# ATmega32.net
KiCad netlist of a schematic drawn in Altium Designer
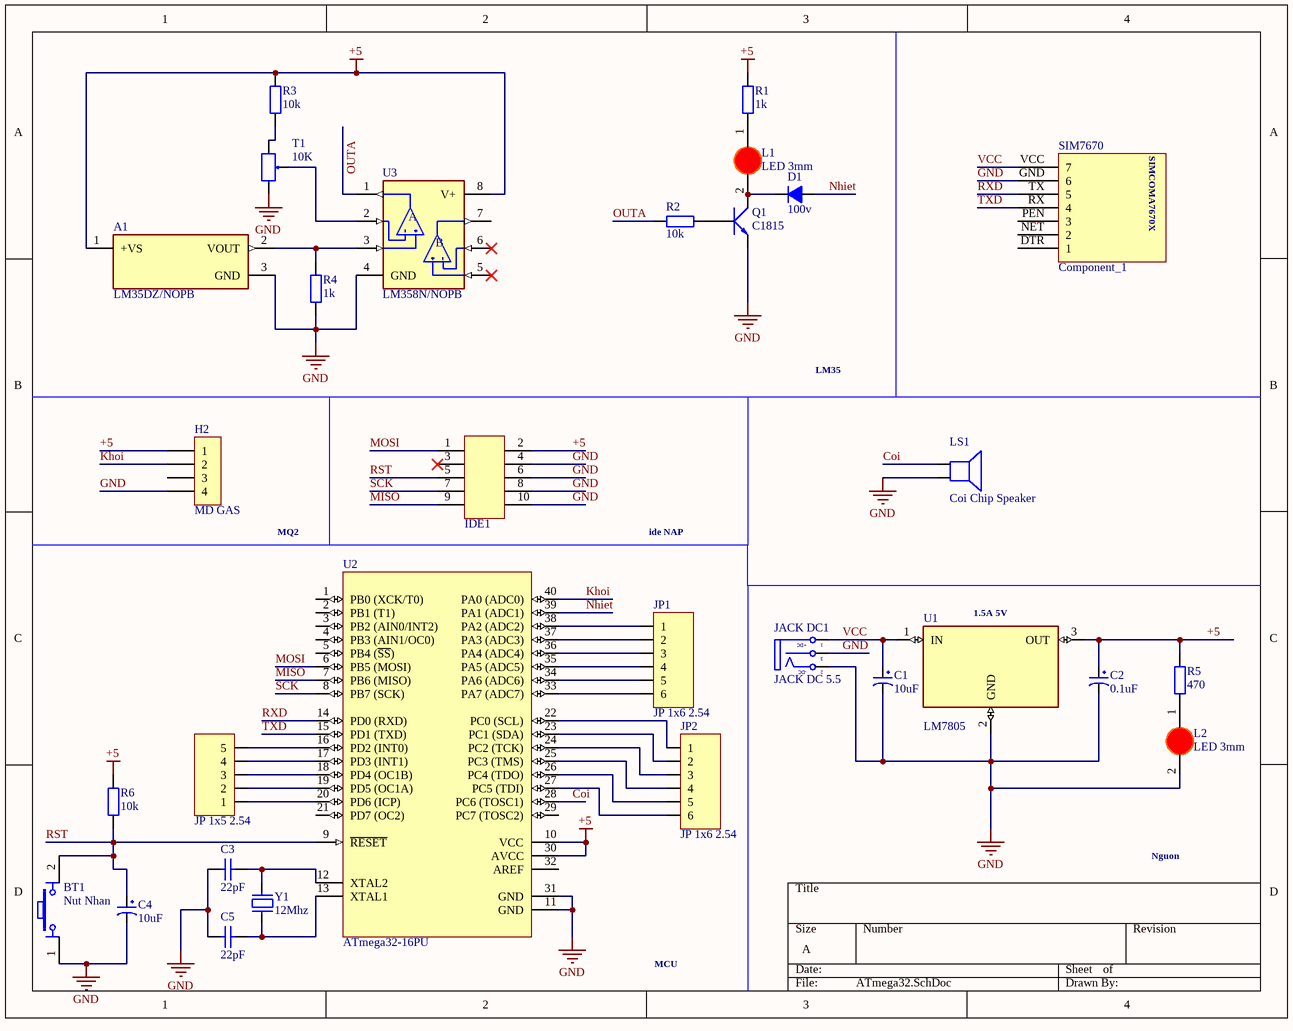
[diagram p0: ATmega32.SchDoc]

(export (version "E")
  (design (tool "Eeschema 10.0.6"))
  (components
    (comp (ref "A1")
      (value "LM35DZ/NOPB")
      (footprint "TO92127P521H735-3")
      (libsource (lib "LM35DZ_NOPB") (part "LM35DZ/NOPB"))
    )
    (comp (ref "BT1")
      (value "Nut Nhan")
      (footprint "Nut Nhan 4 Chan Cam 6x6")
      (description "Nut Nhan 4 Chan 6x6mm")
      (libsource (lib "Altium_Lib") (part "Nut Nhan 4 Chan Cam 6x6"))
    )
    (comp (ref "C1")
      (value "10uF")
      (footprint "tu hoa 4mm")
      (description "Cắm")
      (libsource (lib "Altium_Lib") (part "Tu Hoa 2.2uF 50V 4x7"))
    )
    (comp (ref "C2")
      (value "0.1uF")
      (footprint "tu hoa 4mm")
      (description "Cắm")
      (libsource (lib "Altium_Lib") (part "Tu Hoa 2.2uF 50V 4x7"))
    )
    (comp (ref "C3")
      (value "22pF")
      (footprint "tu gom")
      (description "Cắm")
      (libsource (lib "Altium_Lib") (part "Tu gom 22pF 50V"))
    )
    (comp (ref "C4")
      (value "10uF")
      (footprint "tu hoa 4mm")
      (description "Cắm")
      (libsource (lib "Altium_Lib") (part "Tu Hoa 10uF 25V 4x7"))
    )
    (comp (ref "C5")
      (value "22pF")
      (footprint "tu gom")
      (description "Cắm")
      (libsource (lib "Altium_Lib") (part "Tu gom 22pF 50V"))
    )
    (comp (ref "D1")
      (value "100v")
      (footprint "DIODE 1A")
      (description "Cắm")
      (libsource (lib "Altium_Lib") (part "Diode 1N4007"))
    )
    (comp (ref "H2")
      (value "MD GAS")
      (footprint "Header 4P DC 2.54")
      (description "Cắm")
      (libsource (lib "Altium_Lib") (part "Header 4P 2.54 Duc Cong"))
    )
    (comp (ref "IDE1")
      (value "IDE10")
      (footprint "IDE 10 DT")
      (libsource (lib "Altium_Lib") (part "IDE 10 DT"))
    )
    (comp (ref "JACK DC1")
      (value "JACK DC 5.5")
      (footprint "JACK DC 5.5")
      (libsource (lib "Altium_Lib") (part "JACK DC 5.5"))
    )
    (comp (ref "JP1")
      (value "JP 1x6 2.54")
      (footprint "JP 1x6 DT")
      (description "Cắm")
      (libsource (lib "Altium_Lib") (part "JP 1x6 2.54 Duc Thang"))
    )
    (comp (ref "JP2")
      (value "JP 1x6 2.54")
      (footprint "JP 1x6 DT")
      (description "Cắm")
      (libsource (lib "Altium_Lib") (part "JP 1x6 2.54 Duc Thang"))
    )
    (comp (ref "JP3")
      (value "JP 1x5 2.54")
      (footprint "JP 1x5 DT")
      (description "Cắm")
      (libsource (lib "Altium_Lib") (part "JP 1x5 2.54 Duc Thang"))
    )
    (comp (ref "L1")
      (value "LED 3mm")
      (footprint "LED-3MM-RED")
      (description "Cắm")
      (libsource (lib "Altium_Lib") (part "LED 3mm Do"))
    )
    (comp (ref "L2")
      (value "LED 3mm")
      (footprint "LED-3MM-RED")
      (description "Cắm")
      (libsource (lib "Altium_Lib") (part "LED 3mm Do"))
    )
    (comp (ref "LS1")
      (value "Coi Chip Speaker")
      (footprint "Coi Chip Speacker")
      (description "Còi chip")
      (libsource (lib "Altium_Lib") (part "Coi Chip Speaker"))
    )
    (comp (ref "Q1")
      (value "C1815")
      (footprint "TO92")
      (description "NPN transistor")
      (libsource (lib "Altium_Lib") (part "C1815"))
    )
    (comp (ref "R1")
      (value "1k")
      (footprint "tro vach 1/4w")
      (description "Căm")
      (libsource (lib "Altium_Lib") (part "Tro Vach 1/4W 5% 10k"))
    )
    (comp (ref "R2")
      (value "10k")
      (footprint "tro vach 1/4w")
      (description "Căm")
      (libsource (lib "Altium_Lib") (part "Tro Vach 1/4W 5% 10k"))
    )
    (comp (ref "R3")
      (value "10k")
      (footprint "tro vach 1/4w")
      (description "Căm")
      (libsource (lib "Altium_Lib") (part "Tro Vach 1/4W 5% 10k"))
    )
    (comp (ref "R4")
      (value "1k")
      (footprint "tro vach 1/4w")
      (description "Cắm")
      (libsource (lib "Altium_Lib") (part "Tro Vach 1/4W 5% 1k"))
    )
    (comp (ref "R5")
      (value "470")
      (footprint "tro vach 1/4w")
      (description "Căm")
      (libsource (lib "Altium_Lib") (part "Tro Vach 1/4W 5% 10k"))
    )
    (comp (ref "R6")
      (value "10k")
      (footprint "tro vach 1/4w")
      (description "Cắm")
      (libsource (lib "Altium_Lib") (part "Tro Vach 1/4W 5% 1k"))
    )
    (comp (ref "SIM7670")
      (value "Component_1")
      (footprint "SIM7670X")
      (libsource (lib "SIM7670") (part "Component_1"))
    )
    (comp (ref "T1")
      (value "10K")
      (footprint "Bien Tro Vi Chinh Dung")
      (description "Cắm")
      (libsource (lib "Altium_Lib") (part "Bien Tro Tinh Chinh 10K Dung"))
    )
    (comp (ref "U1")
      (value "LM7805")
      (footprint "TO255P1040X460X1968-3")
      (libsource (lib "LM7805") (part "LM7805"))
    )
    (comp (ref "U2")
      (value "ATmega32-16PU")
      (footprint "40P6")
      (fields (field (name "PARTNUMBER") "ATMEGA32-16PU"))
      (libsource (lib "Microchip_Atmel_ATMEGA32_16PU") (part "ATMEGA32-16PU"))
    )
    (comp (ref "U3")
      (value "LM358N/NOPB")
      (footprint "DIP794W45P254L959H508Q8")
      (libsource (lib "LM358N_NOPB") (part "LM358N/NOPB"))
    )
    (comp (ref "Y1")
      (value "12Mhz")
      (footprint "Thach Anh 2 chan cam")
      (description "Crystal For all Crystal 2pin.")
      (libsource (lib "Altium_Lib") (part "Thach Anh 2 chan Cam"))
    )
  )
  (nets
    (net (code "1") (name "+5") (class "Default")
      (node (ref "A1") (pin "1") (pinfunction "+VS_1") (pintype "power_in"))
      (node (ref "C2") (pin "1") (pinfunction "1_1") (pintype "passive"))
      (node (ref "H2") (pin "1") (pinfunction "1_1") (pintype "passive"))
      (node (ref "IDE1") (pin "2") (pinfunction "2_2") (pintype "passive"))
      (node (ref "R1") (pin "2") (pinfunction "2_2") (pintype "passive"))
      (node (ref "R3") (pin "2") (pinfunction "2_2") (pintype "passive"))
      (node (ref "R5") (pin "2") (pinfunction "2_2") (pintype "passive"))
      (node (ref "R6") (pin "2") (pinfunction "2_2") (pintype "passive"))
      (node (ref "U1") (pin "3") (pinfunction "OUT_3") (pintype "bidirectional"))
      (node (ref "U2") (pin "10") (pinfunction "VCC_10") (pintype "power_in"))
      (node (ref "U2") (pin "30") (pinfunction "AVCC_30") (pintype "power_in"))
      (node (ref "U3") (pin "8") (pinfunction "V+_8") (pintype "power_in"))
    )
    (net (code "2") (name "/Coi") (class "Default")
      (node (ref "LS1") (pin "1") (pinfunction "1_1") (pintype "passive"))
      (node (ref "U2") (pin "28") (pinfunction "PC6_(TOSC1)_28") (pintype "bidirectional"))
    )
    (net (code "3") (name "/Khoi") (class "Default")
      (node (ref "H2") (pin "2") (pinfunction "2_2") (pintype "passive"))
      (node (ref "U2") (pin "40") (pinfunction "PA0_(ADC0)_40") (pintype "bidirectional"))
    )
    (net (code "4") (name "/MISO") (class "Default")
      (node (ref "IDE1") (pin "9") (pinfunction "9_9") (pintype "passive"))
      (node (ref "U2") (pin "7") (pinfunction "PB6_(MISO)_7") (pintype "bidirectional"))
    )
    (net (code "5") (name "/MOSI") (class "Default")
      (node (ref "IDE1") (pin "1") (pinfunction "1_1") (pintype "passive"))
      (node (ref "U2") (pin "6") (pinfunction "PB5_(MOSI)_6") (pintype "bidirectional"))
    )
    (net (code "6") (name "/Nhiet") (class "Default")
      (node (ref "D1") (pin "1") (pinfunction "A_1") (pintype "passive"))
      (node (ref "U2") (pin "39") (pinfunction "PA1_(ADC1)_39") (pintype "bidirectional"))
    )
    (net (code "7") (name "/OUTA") (class "Default")
      (node (ref "R2") (pin "1") (pinfunction "1_1") (pintype "passive"))
      (node (ref "U3") (pin "1") (pinfunction "OUTA_1") (pintype "output"))
    )
    (net (code "8") (name "/RST") (class "Default")
      (node (ref "BT1") (pin "2") (pintype "passive"))
      (node (ref "C4") (pin "1") (pinfunction "1_1") (pintype "passive"))
      (node (ref "IDE1") (pin "5") (pinfunction "5_5") (pintype "passive"))
      (node (ref "R6") (pin "1") (pinfunction "1_1") (pintype "passive"))
      (node (ref "U2") (pin "9") (pinfunction "~{RESET}_9") (pintype "input"))
    )
    (net (code "9") (name "/RXD") (class "Default")
      (node (ref "SIM7670") (pin "TX") (pinfunction "5_TX") (pintype "passive"))
      (node (ref "U2") (pin "14") (pinfunction "PD0_(RXD)_14") (pintype "bidirectional"))
    )
    (net (code "10") (name "/SCK") (class "Default")
      (node (ref "IDE1") (pin "7") (pinfunction "7_7") (pintype "passive"))
      (node (ref "U2") (pin "8") (pinfunction "PB7_(SCK)_8") (pintype "bidirectional"))
    )
    (net (code "11") (name "/TXD") (class "Default")
      (node (ref "SIM7670") (pin "RX") (pinfunction "4_RX") (pintype "passive"))
      (node (ref "U2") (pin "15") (pinfunction "PD1_(TXD)_15") (pintype "bidirectional"))
    )
    (net (code "12") (name "/VCC") (class "Default")
      (node (ref "C1") (pin "1") (pinfunction "1_1") (pintype "passive"))
      (node (ref "JACK DC1") (pin "1") (pinfunction "T_1") (pintype "passive"))
      (node (ref "SIM7670") (pin "VCC") (pinfunction "7_VCC") (pintype "passive"))
      (node (ref "U1") (pin "1") (pinfunction "IN_1") (pintype "bidirectional"))
    )
    (net (code "13") (name "GND") (class "Default")
      (node (ref "A1") (pin "3") (pinfunction "GND_3") (pintype "power_in"))
      (node (ref "BT1") (pin "1") (pintype "passive"))
      (node (ref "C1") (pin "2") (pinfunction "2_2") (pintype "passive"))
      (node (ref "C2") (pin "2") (pinfunction "2_2") (pintype "passive"))
      (node (ref "C3") (pin "2") (pinfunction "2_2") (pintype "passive"))
      (node (ref "C4") (pin "2") (pinfunction "2_2") (pintype "passive"))
      (node (ref "C5") (pin "2") (pinfunction "2_2") (pintype "passive"))
      (node (ref "H2") (pin "4") (pinfunction "4_4") (pintype "passive"))
      (node (ref "IDE1") (pin "10") (pinfunction "10_10") (pintype "passive"))
      (node (ref "IDE1") (pin "4") (pinfunction "4_4") (pintype "passive"))
      (node (ref "IDE1") (pin "6") (pinfunction "6_6") (pintype "passive"))
      (node (ref "IDE1") (pin "8") (pinfunction "8_8") (pintype "passive"))
      (node (ref "JACK DC1") (pin "2") (pinfunction "TN_2") (pintype "passive"))
      (node (ref "JACK DC1") (pin "3") (pinfunction "S_3") (pintype "power_in"))
      (node (ref "L2") (pin "2") (pinfunction "K_2") (pintype "passive"))
      (node (ref "LS1") (pin "2") (pinfunction "2_2") (pintype "passive"))
      (node (ref "Q1") (pin "1") (pinfunction "E_1") (pintype "passive"))
      (node (ref "R4") (pin "1") (pinfunction "1_1") (pintype "passive"))
      (node (ref "SIM7670") (pin "GND") (pinfunction "6_GND") (pintype "passive"))
      (node (ref "T1") (pin "3") (pinfunction "3_3") (pintype "passive"))
      (node (ref "U1") (pin "2") (pinfunction "GND_2") (pintype "bidirectional"))
      (node (ref "U2") (pin "11") (pinfunction "GND_11") (pintype "power_in"))
      (node (ref "U2") (pin "31") (pinfunction "GND_31") (pintype "power_in"))
      (node (ref "U3") (pin "4") (pinfunction "GND_4") (pintype "power_in"))
    )
    (net (code "14") (name "Net-(A1-VOUT)") (class "Default")
      (node (ref "A1") (pin "2") (pinfunction "VOUT_2") (pintype "output"))
      (node (ref "R4") (pin "2") (pinfunction "2_2") (pintype "passive"))
      (node (ref "U3") (pin "3") (pinfunction "+INA_3") (pintype "input"))
    )
    (net (code "15") (name "Net-(D1-K)") (class "Default")
      (node (ref "D1") (pin "2") (pinfunction "K_2") (pintype "passive"))
      (node (ref "L1") (pin "2") (pinfunction "K_2") (pintype "passive"))
      (node (ref "Q1") (pin "2") (pinfunction "C_2") (pintype "passive"))
    )
    (net (code "16") (name "Net-(L1-A)") (class "Default")
      (node (ref "L1") (pin "1") (pinfunction "A_1") (pintype "passive"))
      (node (ref "R1") (pin "1") (pinfunction "1_1") (pintype "passive"))
    )
    (net (code "17") (name "Net-(L2-A)") (class "Default")
      (node (ref "L2") (pin "1") (pinfunction "A_1") (pintype "passive"))
      (node (ref "R5") (pin "1") (pinfunction "1_1") (pintype "passive"))
    )
    (net (code "18") (name "Net-(Q1-B)") (class "Default")
      (node (ref "Q1") (pin "3") (pinfunction "B_3") (pintype "passive"))
      (node (ref "R2") (pin "2") (pinfunction "2_2") (pintype "passive"))
    )
    (net (code "19") (name "Net-(R3-Pad1)") (class "Default")
      (node (ref "R3") (pin "1") (pinfunction "1_1") (pintype "passive"))
      (node (ref "T1") (pin "1") (pinfunction "1_1") (pintype "passive"))
    )
    (net (code "20") (name "Net-(U2-PA2_(ADC2))") (class "Default")
      (node (ref "JP1") (pin "1") (pinfunction "1_1") (pintype "passive"))
      (node (ref "U2") (pin "38") (pinfunction "PA2_(ADC2)_38") (pintype "bidirectional"))
    )
    (net (code "21") (name "Net-(U2-PA3_(ADC3))") (class "Default")
      (node (ref "JP1") (pin "2") (pinfunction "2_2") (pintype "passive"))
      (node (ref "U2") (pin "37") (pinfunction "PA3_(ADC3)_37") (pintype "bidirectional"))
    )
    (net (code "22") (name "Net-(U2-PA4_(ADC4))") (class "Default")
      (node (ref "JP1") (pin "3") (pinfunction "3_3") (pintype "passive"))
      (node (ref "U2") (pin "36") (pinfunction "PA4_(ADC4)_36") (pintype "bidirectional"))
    )
    (net (code "23") (name "Net-(U2-PA5_(ADC5))") (class "Default")
      (node (ref "JP1") (pin "4") (pinfunction "4_4") (pintype "passive"))
      (node (ref "U2") (pin "35") (pinfunction "PA5_(ADC5)_35") (pintype "bidirectional"))
    )
    (net (code "24") (name "Net-(U2-PA6_(ADC6))") (class "Default")
      (node (ref "JP1") (pin "5") (pinfunction "5_5") (pintype "passive"))
      (node (ref "U2") (pin "34") (pinfunction "PA6_(ADC6)_34") (pintype "bidirectional"))
    )
    (net (code "25") (name "Net-(U2-PA7_(ADC7))") (class "Default")
      (node (ref "JP1") (pin "6") (pinfunction "6_6") (pintype "passive"))
      (node (ref "U2") (pin "33") (pinfunction "PA7_(ADC7)_33") (pintype "bidirectional"))
    )
    (net (code "26") (name "Net-(U2-PC0_(SCL))") (class "Default")
      (node (ref "JP2") (pin "1") (pinfunction "1_1") (pintype "passive"))
      (node (ref "U2") (pin "22") (pinfunction "PC0_(SCL)_22") (pintype "bidirectional"))
    )
    (net (code "27") (name "Net-(U2-PC1_(SDA))") (class "Default")
      (node (ref "JP2") (pin "2") (pinfunction "2_2") (pintype "passive"))
      (node (ref "U2") (pin "23") (pinfunction "PC1_(SDA)_23") (pintype "bidirectional"))
    )
    (net (code "28") (name "Net-(U2-PC2_(TCK))") (class "Default")
      (node (ref "JP2") (pin "3") (pinfunction "3_3") (pintype "passive"))
      (node (ref "U2") (pin "24") (pinfunction "PC2_(TCK)_24") (pintype "bidirectional"))
    )
    (net (code "29") (name "Net-(U2-PC3_(TMS))") (class "Default")
      (node (ref "JP2") (pin "4") (pinfunction "4_4") (pintype "passive"))
      (node (ref "U2") (pin "25") (pinfunction "PC3_(TMS)_25") (pintype "bidirectional"))
    )
    (net (code "30") (name "Net-(U2-PC4_(TDO))") (class "Default")
      (node (ref "JP2") (pin "5") (pinfunction "5_5") (pintype "passive"))
      (node (ref "U2") (pin "26") (pinfunction "PC4_(TDO)_26") (pintype "bidirectional"))
    )
    (net (code "31") (name "Net-(U2-PC5_(TDI))") (class "Default")
      (node (ref "JP2") (pin "6") (pinfunction "6_6") (pintype "passive"))
      (node (ref "U2") (pin "27") (pinfunction "PC5_(TDI)_27") (pintype "bidirectional"))
    )
    (net (code "32") (name "Net-(U2-PD2_(INT0))") (class "Default")
      (node (ref "JP3") (pin "5") (pinfunction "5_5") (pintype "passive"))
      (node (ref "U2") (pin "16") (pinfunction "PD2_(INT0)_16") (pintype "bidirectional"))
    )
    (net (code "33") (name "Net-(U2-PD3_(INT1))") (class "Default")
      (node (ref "JP3") (pin "4") (pinfunction "4_4") (pintype "passive"))
      (node (ref "U2") (pin "17") (pinfunction "PD3_(INT1)_17") (pintype "bidirectional"))
    )
    (net (code "34") (name "Net-(U2-PD4_(OC1B))") (class "Default")
      (node (ref "JP3") (pin "3") (pinfunction "3_3") (pintype "passive"))
      (node (ref "U2") (pin "18") (pinfunction "PD4_(OC1B)_18") (pintype "bidirectional"))
    )
    (net (code "35") (name "Net-(U2-PD5_(OC1A))") (class "Default")
      (node (ref "JP3") (pin "2") (pinfunction "2_2") (pintype "passive"))
      (node (ref "U2") (pin "19") (pinfunction "PD5_(OC1A)_19") (pintype "bidirectional"))
    )
    (net (code "36") (name "Net-(U2-PD6_(ICP))") (class "Default")
      (node (ref "JP3") (pin "1") (pinfunction "1_1") (pintype "passive"))
      (node (ref "U2") (pin "20") (pinfunction "PD6_(ICP)_20") (pintype "bidirectional"))
    )
    (net (code "37") (name "Net-(U2-XTAL1)") (class "Default")
      (node (ref "C5") (pin "1") (pinfunction "1_1") (pintype "passive"))
      (node (ref "U2") (pin "13") (pinfunction "XTAL1_13") (pintype "passive"))
      (node (ref "Y1") (pin "1") (pinfunction "1_1") (pintype "passive"))
    )
    (net (code "38") (name "Net-(U2-XTAL2)") (class "Default")
      (node (ref "C3") (pin "1") (pinfunction "1_1") (pintype "passive"))
      (node (ref "U2") (pin "12") (pinfunction "XTAL2_12") (pintype "passive"))
      (node (ref "Y1") (pin "2") (pinfunction "2_2") (pintype "passive"))
    )
    (net (code "39") (name "Net-(U3--INA)") (class "Default")
      (node (ref "T1") (pin "2") (pinfunction "2_2") (pintype "passive"))
      (node (ref "U3") (pin "2") (pinfunction "-INA_2") (pintype "input"))
    )
    (net (code "40") (name "unconnected-(H2-Pad3)") (class "Default")
      (node (ref "H2") (pin "3") (pinfunction "3_3") (pintype "passive"))
    )
    (net (code "41") (name "unconnected-(IDE1-Pad3)") (class "Default")
      (node (ref "IDE1") (pin "3") (pinfunction "3_3") (pintype "passive+no_connect"))
    )
    (net (code "42") (name "unconnected-(SIM7670-1-PadDTR)") (class "Default")
      (node (ref "SIM7670") (pin "DTR") (pinfunction "1_DTR") (pintype "passive"))
    )
    (net (code "43") (name "unconnected-(SIM7670-2-PadNET)") (class "Default")
      (node (ref "SIM7670") (pin "NET") (pinfunction "2_NET") (pintype "passive"))
    )
    (net (code "44") (name "unconnected-(SIM7670-3-PadPEN)") (class "Default")
      (node (ref "SIM7670") (pin "PEN") (pinfunction "3_PEN") (pintype "passive"))
    )
    (net (code "45") (name "unconnected-(U2-AREF-Pad32)") (class "Default")
      (node (ref "U2") (pin "32") (pinfunction "AREF_32") (pintype "passive"))
    )
    (net (code "46") (name "unconnected-(U2-PB0_(XCK{slash}T0)-Pad1)") (class "Default")
      (node (ref "U2") (pin "1") (pinfunction "PB0_(XCK/T0)_1") (pintype "bidirectional"))
    )
    (net (code "47") (name "unconnected-(U2-PB1_(T1)-Pad2)") (class "Default")
      (node (ref "U2") (pin "2") (pinfunction "PB1_(T1)_2") (pintype "bidirectional"))
    )
    (net (code "48") (name "unconnected-(U2-PB2_(AIN0{slash}INT2)-Pad3)") (class "Default")
      (node (ref "U2") (pin "3") (pinfunction "PB2_(AIN0/INT2)_3") (pintype "bidirectional"))
    )
    (net (code "49") (name "unconnected-(U2-PB3_(AIN1{slash}OC0)-Pad4)") (class "Default")
      (node (ref "U2") (pin "4") (pinfunction "PB3_(AIN1/OC0)_4") (pintype "bidirectional"))
    )
    (net (code "50") (name "unconnected-(U2-PB4_(~{SS})-Pad5)") (class "Default")
      (node (ref "U2") (pin "5") (pinfunction "PB4_(~{SS})_5") (pintype "bidirectional"))
    )
    (net (code "51") (name "unconnected-(U2-PC7_(TOSC2)-Pad29)") (class "Default")
      (node (ref "U2") (pin "29") (pinfunction "PC7_(TOSC2)_29") (pintype "bidirectional"))
    )
    (net (code "52") (name "unconnected-(U2-PD7_(OC2)-Pad21)") (class "Default")
      (node (ref "U2") (pin "21") (pinfunction "PD7_(OC2)_21") (pintype "bidirectional"))
    )
    (net (code "53") (name "unconnected-(U3-+INB-Pad5)") (class "Default")
      (node (ref "U3") (pin "5") (pinfunction "+INB_5") (pintype "input+no_connect"))
    )
    (net (code "54") (name "unconnected-(U3--INB-Pad6)") (class "Default")
      (node (ref "U3") (pin "6") (pinfunction "-INB_6") (pintype "input+no_connect"))
    )
    (net (code "55") (name "unconnected-(U3-OUTB-Pad7)") (class "Default")
      (node (ref "U3") (pin "7") (pinfunction "OUTB_7") (pintype "output"))
    )
  )
)
